# Battery.net
KiCad netlist of a schematic drawn in Altium Designer
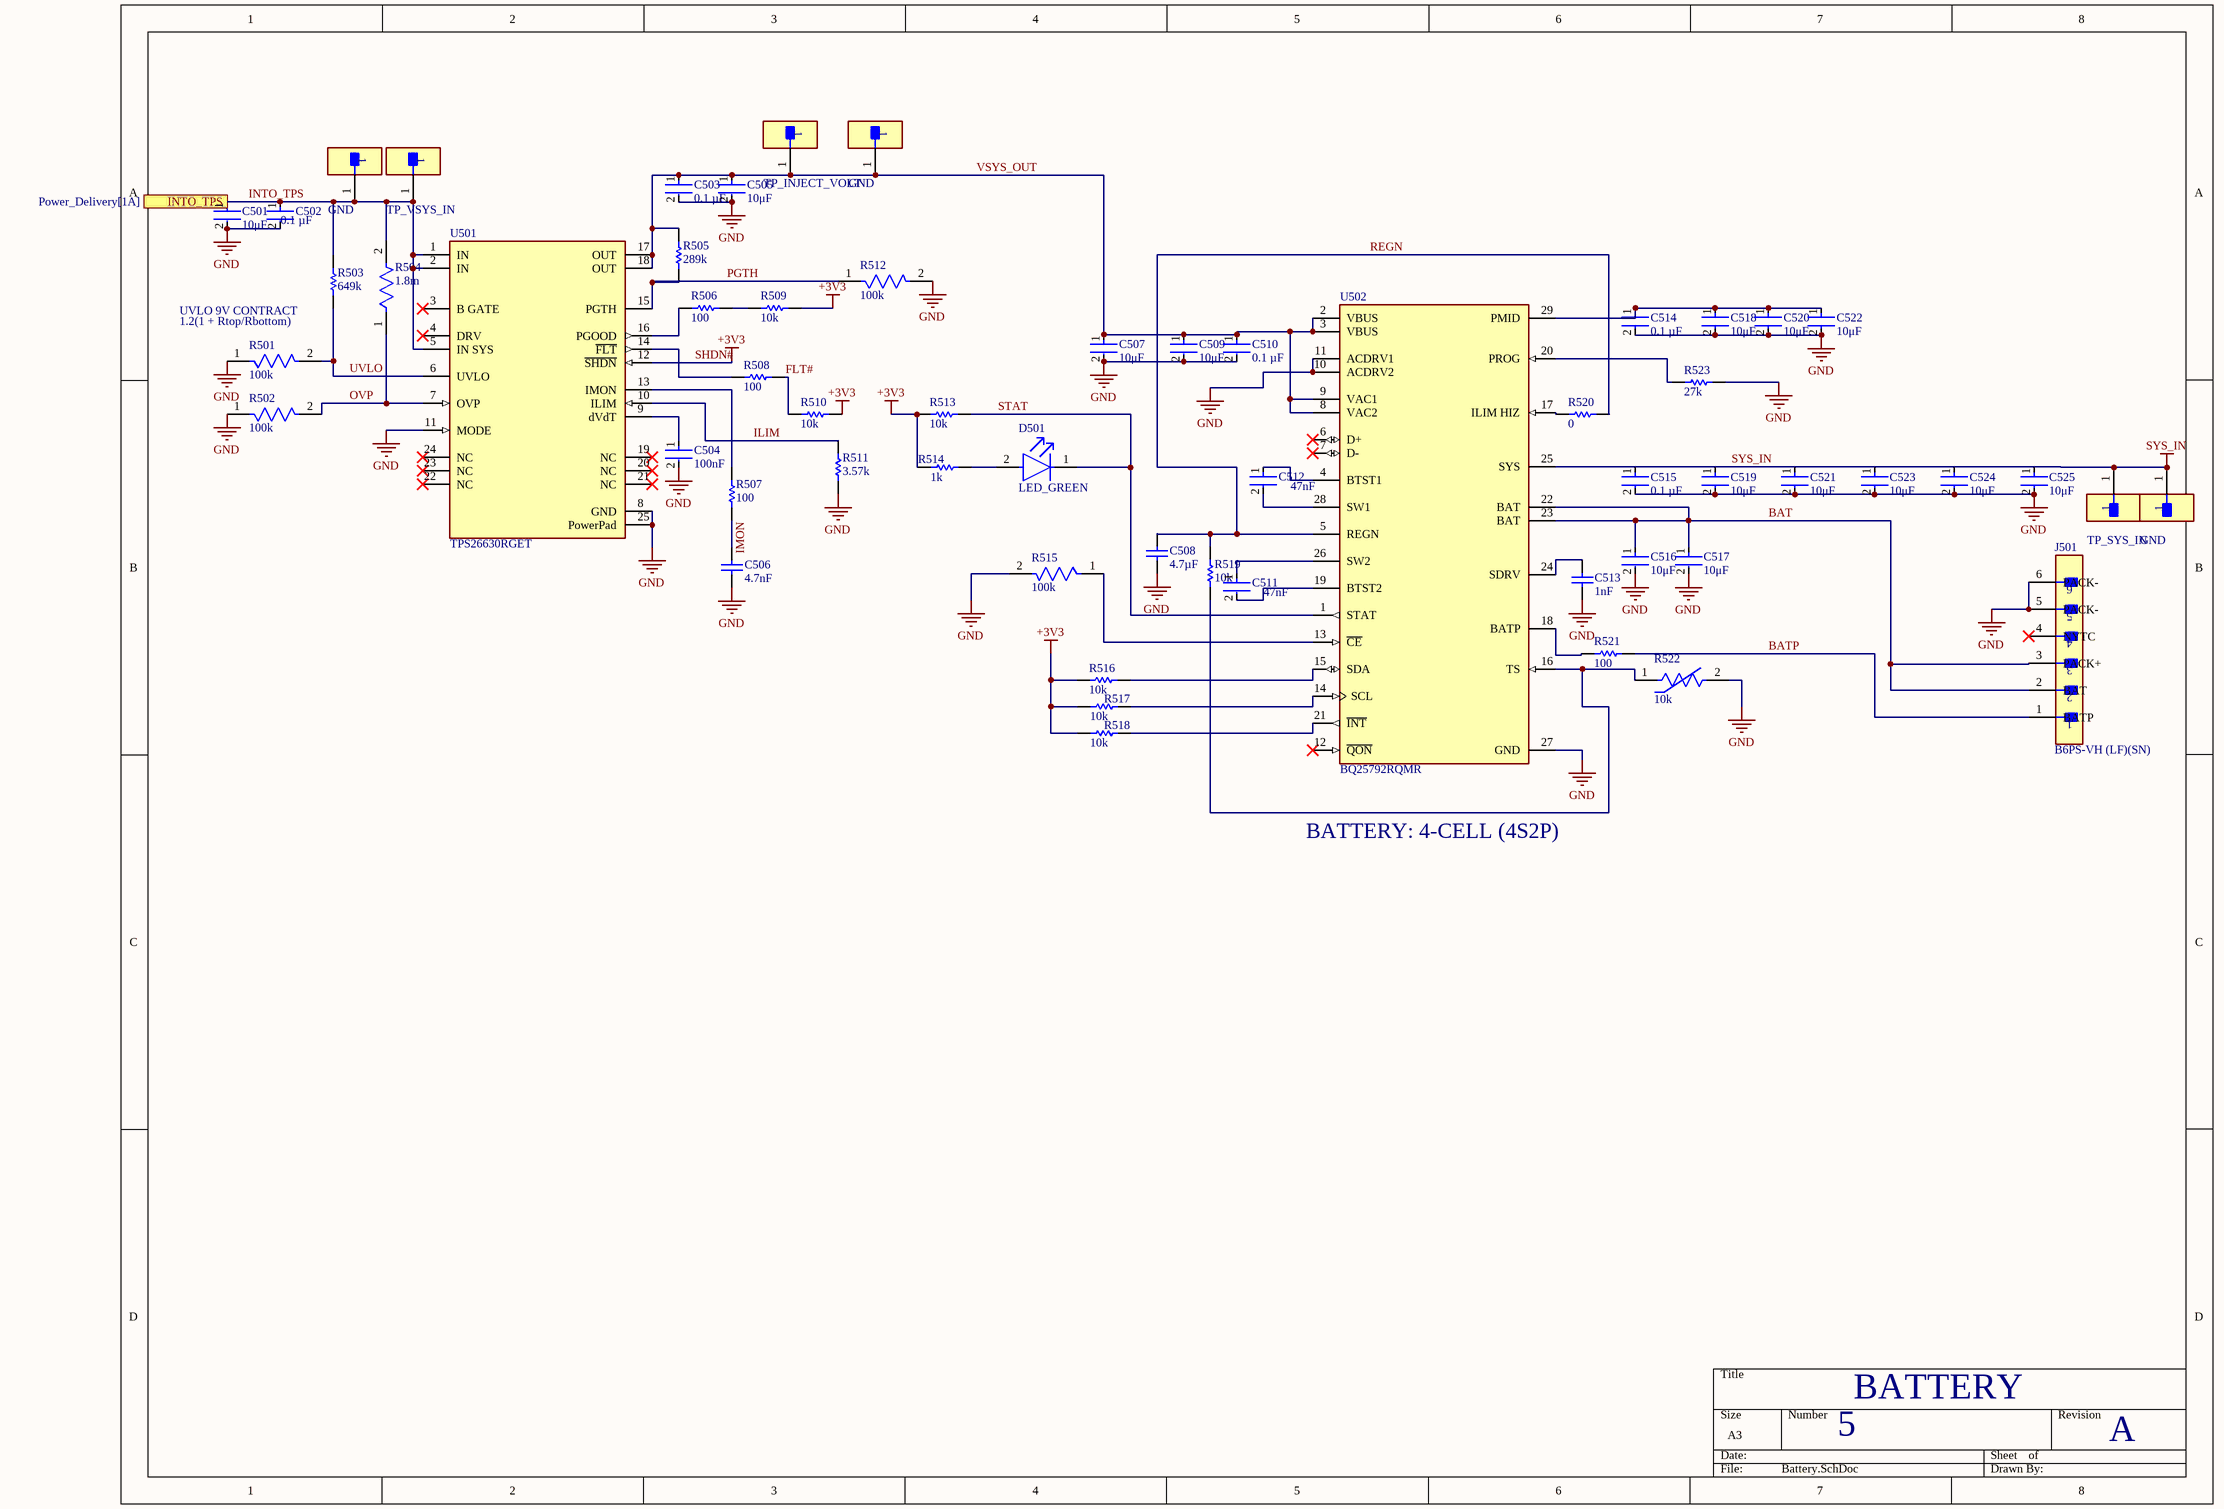
[diagram p0: Battery.SchDoc]

(export (version "E")
  (design (tool "Eeschema 10.0.6"))
  (components
    (comp (ref "C501")
      (value "10μF")
      (footprint "FP-GRM31C-0_2-e0_3_0_8-MFG")
      (description "Chip Multilayer Ceramic Capacitors for General Purpose, 1206, 10uF, X7R, 15%, 10%, 25V")
      (fields (field (name "TOLERANCE") "10%") (field (name "VOLTAGE") "25V"))
      (libsource (lib "Altium Content Vault") (part "02cd4be3c70576c341d710602a673aa"))
    )
    (comp (ref "C502")
      (value "0.1 µF")
      (footprint "FP-GRM155-0_05-IPC_B")
      (description "Chip Multilayer Ceramic Capacitors for General Purpose, 0402, 0.10uF, X7R, 15%, 10%, 50V")
      (fields (field (name "TOLERANCE") "10%"))
      (libsource (lib "Altium Content Vault") (part "02cd4be3c70576c341d710602a673aa"))
    )
    (comp (ref "C503")
      (value "0.1 µF")
      (footprint "FP-GRM155-0_05-IPC_B")
      (description "Chip Multilayer Ceramic Capacitors for General Purpose, 0402, 0.10uF, X7R, 15%, 10%, 50V")
      (fields (field (name "TOLERANCE") "10%"))
      (libsource (lib "Altium Content Vault") (part "02cd4be3c70576c341d710602a673aa"))
    )
    (comp (ref "C504")
      (value "100nF")
      (footprint "FP-GRM155-0_05-IPC_C")
      (description "Chip Multilayer Ceramic Capacitors for General Purpose, 0402, 0.10uF, X7R, 15%, 10%, 25V")
      (fields (field (name "TOLERANCE") "10%"))
      (libsource (lib "Altium Content Vault") (part "02cd4be3c70576c341d710602a673aa"))
    )
    (comp (ref "C505")
      (value "10μF")
      (footprint "FP-GRM31C-0_2-e0_3_0_8-MFG")
      (description "Chip Multilayer Ceramic Capacitors for General Purpose, 1206, 10uF, X7R, 15%, 10%, 25V")
      (fields (field (name "TOLERANCE") "10%") (field (name "VOLTAGE") "25V"))
      (libsource (lib "Altium Content Vault") (part "02cd4be3c70576c341d710602a673aa"))
    )
    (comp (ref "C506")
      (value "4.7nF")
      (footprint "CAPC1005X55X25LL05T10")
      (fields (field (name "MANUFACTURER") "Murata") (field (name "PART NUMBER") "GRM155R71C472KA01D"))
      (libsource (lib "Altium Content Vault") (part "CAP"))
    )
    (comp (ref "C507")
      (value "10μF")
      (footprint "FP-GRM31C-0_2-e0_3_0_8-MFG")
      (description "Chip Multilayer Ceramic Capacitors for General Purpose, 1206, 10uF, X7R, 15%, 10%, 25V")
      (fields (field (name "TOLERANCE") "10%") (field (name "VOLTAGE") "25V"))
      (libsource (lib "Altium Content Vault") (part "02cd4be3c70576c341d710602a673aa"))
    )
    (comp (ref "C508")
      (value "4.7µF")
      (footprint "CAPC1608X90X35NL10T15")
      (fields (field (name "MANUFACTURER") "Murata") (field (name "PART NUMBER") "GRM188R61A475KE15D"))
      (libsource (lib "Altium Content Vault") (part "CAP"))
    )
    (comp (ref "C509")
      (value "10μF")
      (footprint "FP-GRM31C-0_2-e0_3_0_8-MFG")
      (description "Chip Multilayer Ceramic Capacitors for General Purpose, 1206, 10uF, X7R, 15%, 10%, 25V")
      (fields (field (name "TOLERANCE") "10%") (field (name "VOLTAGE") "25V"))
      (libsource (lib "Altium Content Vault") (part "02cd4be3c70576c341d710602a673aa"))
    )
    (comp (ref "C510")
      (value "0.1 µF")
      (footprint "FP-GRM155-0_05-IPC_B")
      (description "Chip Multilayer Ceramic Capacitors for General Purpose, 0402, 0.10uF, X7R, 15%, 10%, 50V")
      (fields (field (name "TOLERANCE") "10%"))
      (libsource (lib "Altium Content Vault") (part "02cd4be3c70576c341d710602a673aa"))
    )
    (comp (ref "C511")
      (value "47nF")
      (footprint "FP-GRM155-0_05-MFG")
      (description "Chip Multilayer Ceramic Capacitors for General Purpose, 0402, 47000pF, X7R, 15%, 10%, 50V")
      (fields (field (name "TOLERANCE") "10%"))
      (libsource (lib "Altium Content Vault") (part "02cd4be3c70576c341d710602a673aa"))
    )
    (comp (ref "C512")
      (value "47nF")
      (footprint "FP-GRM155-0_05-MFG")
      (description "Chip Multilayer Ceramic Capacitors for General Purpose, 0402, 47000pF, X7R, 15%, 10%, 50V")
      (fields (field (name "TOLERANCE") "10%"))
      (libsource (lib "Altium Content Vault") (part "02cd4be3c70576c341d710602a673aa"))
    )
    (comp (ref "C513")
      (value "1nF")
      (footprint "CAPC1005X55X25ML5T10")
      (description "Chip Capacitor, 1 nF, +/- 10%, 50 V, -55 to 125 degC, 0402 (1005 Metric), RoHS, Tape and Reel")
      (fields (field (name "TOLERANCE") "10%"))
      (libsource (lib "Altium Content Vault") (part "CAP-NP-2"))
    )
    (comp (ref "C514")
      (value "0.1 µF")
      (footprint "FP-GRM155-0_05-IPC_B")
      (description "Chip Multilayer Ceramic Capacitors for General Purpose, 0402, 0.10uF, X7R, 15%, 10%, 50V")
      (fields (field (name "TOLERANCE") "10%"))
      (libsource (lib "Altium Content Vault") (part "02cd4be3c70576c341d710602a673aa"))
    )
    (comp (ref "C515")
      (value "0.1 µF")
      (footprint "FP-GRM155-0_05-IPC_B")
      (description "Chip Multilayer Ceramic Capacitors for General Purpose, 0402, 0.10uF, X7R, 15%, 10%, 50V")
      (fields (field (name "TOLERANCE") "10%"))
      (libsource (lib "Altium Content Vault") (part "02cd4be3c70576c341d710602a673aa"))
    )
    (comp (ref "C516")
      (value "10μF")
      (footprint "FP-GRM31C-0_2-e0_3_0_8-MFG")
      (description "Chip Multilayer Ceramic Capacitors for General Purpose, 1206, 10uF, X7R, 15%, 10%, 25V")
      (fields (field (name "TOLERANCE") "10%") (field (name "VOLTAGE") "25V"))
      (libsource (lib "Altium Content Vault") (part "02cd4be3c70576c341d710602a673aa"))
    )
    (comp (ref "C517")
      (value "10μF")
      (footprint "FP-GRM31C-0_2-e0_3_0_8-MFG")
      (description "Chip Multilayer Ceramic Capacitors for General Purpose, 1206, 10uF, X7R, 15%, 10%, 25V")
      (fields (field (name "TOLERANCE") "10%") (field (name "VOLTAGE") "25V"))
      (libsource (lib "Altium Content Vault") (part "02cd4be3c70576c341d710602a673aa"))
    )
    (comp (ref "C518")
      (value "10μF")
      (footprint "FP-GRM31C-0_2-e0_3_0_8-MFG")
      (description "Chip Multilayer Ceramic Capacitors for General Purpose, 1206, 10uF, X7R, 15%, 10%, 25V")
      (fields (field (name "TOLERANCE") "10%") (field (name "VOLTAGE") "25V"))
      (libsource (lib "Altium Content Vault") (part "02cd4be3c70576c341d710602a673aa"))
    )
    (comp (ref "C519")
      (value "10μF")
      (footprint "FP-GRM31C-0_2-e0_3_0_8-MFG")
      (description "Chip Multilayer Ceramic Capacitors for General Purpose, 1206, 10uF, X7R, 15%, 10%, 25V")
      (fields (field (name "TOLERANCE") "10%") (field (name "VOLTAGE") "25V"))
      (libsource (lib "Altium Content Vault") (part "02cd4be3c70576c341d710602a673aa"))
    )
    (comp (ref "C520")
      (value "10μF")
      (footprint "FP-GRM31C-0_2-e0_3_0_8-MFG")
      (description "Chip Multilayer Ceramic Capacitors for General Purpose, 1206, 10uF, X7R, 15%, 10%, 25V")
      (fields (field (name "TOLERANCE") "10%") (field (name "VOLTAGE") "25V"))
      (libsource (lib "Altium Content Vault") (part "02cd4be3c70576c341d710602a673aa"))
    )
    (comp (ref "C521")
      (value "10μF")
      (footprint "FP-GRM31C-0_2-e0_3_0_8-MFG")
      (description "Chip Multilayer Ceramic Capacitors for General Purpose, 1206, 10uF, X7R, 15%, 10%, 25V")
      (fields (field (name "TOLERANCE") "10%") (field (name "VOLTAGE") "25V"))
      (libsource (lib "Altium Content Vault") (part "02cd4be3c70576c341d710602a673aa"))
    )
    (comp (ref "C522")
      (value "10μF")
      (footprint "FP-GRM31C-0_2-e0_3_0_8-MFG")
      (description "Chip Multilayer Ceramic Capacitors for General Purpose, 1206, 10uF, X7R, 15%, 10%, 25V")
      (fields (field (name "TOLERANCE") "10%") (field (name "VOLTAGE") "25V"))
      (libsource (lib "Altium Content Vault") (part "02cd4be3c70576c341d710602a673aa"))
    )
    (comp (ref "C523")
      (value "10μF")
      (footprint "FP-GRM31C-0_2-e0_3_0_8-MFG")
      (description "Chip Multilayer Ceramic Capacitors for General Purpose, 1206, 10uF, X7R, 15%, 10%, 25V")
      (fields (field (name "TOLERANCE") "10%") (field (name "VOLTAGE") "25V"))
      (libsource (lib "Altium Content Vault") (part "02cd4be3c70576c341d710602a673aa"))
    )
    (comp (ref "C524")
      (value "10μF")
      (footprint "FP-GRM31C-0_2-e0_3_0_8-MFG")
      (description "Chip Multilayer Ceramic Capacitors for General Purpose, 1206, 10uF, X7R, 15%, 10%, 25V")
      (fields (field (name "TOLERANCE") "10%") (field (name "VOLTAGE") "25V"))
      (libsource (lib "Altium Content Vault") (part "02cd4be3c70576c341d710602a673aa"))
    )
    (comp (ref "C525")
      (value "10μF")
      (footprint "FP-GRM31C-0_2-e0_3_0_8-MFG")
      (description "Chip Multilayer Ceramic Capacitors for General Purpose, 1206, 10uF, X7R, 15%, 10%, 25V")
      (fields (field (name "TOLERANCE") "10%") (field (name "VOLTAGE") "25V"))
      (libsource (lib "Altium Content Vault") (part "02cd4be3c70576c341d710602a673aa"))
    )
    (comp (ref "D501")
      (value "LED_GREEN")
      (footprint "FP-SML-D12-MFG")
      (description "LED YLW/GREEN DIFFUSED 1608 SMD")
      (fields (field (name "MANUFACTURER PART NUMBER") "SML-D12M1WT86") (field (name "MANUFACTURER") "Rohm"))
      (libsource (lib "Altium Content Vault") (part "8706943c75ba83719d021d2fdc84c58"))
    )
    (comp (ref "J501")
      (value "B6PS-VH (LF)(SN)")
      (footprint "FP-B6PS-VH_LF_SN-MFG")
      (description "CONN HEADER R/A 6POS 3.96MM")
      (libsource (lib "Altium Content Vault") (part "f2cb566baf1c37ab5a3b8e90bbeafd6"))
    )
    (comp (ref "R501")
      (value "100k")
      (footprint "FP-RC0402-0_4-IPC_A")
      (description "RES 100K OHM 5% 1/16W 0402")
      (fields (field (name "TOLERANCE") "5%"))
      (libsource (lib "Altium Content Vault") (part "1029c3af85768c4190bb7ad29bc67b5"))
    )
    (comp (ref "R502")
      (value "100k")
      (footprint "FP-RC0402-0_4-IPC_A")
      (description "RES 100K OHM 5% 1/16W 0402")
      (fields (field (name "TOLERANCE") "5%"))
      (libsource (lib "Altium Content Vault") (part "1029c3af85768c4190bb7ad29bc67b5"))
    )
    (comp (ref "R503")
      (value "649k")
      (footprint "RESC1005X40X25ML05T10")
      (fields (field (name "PART NUMBER") "RC0402FR-07649KL") (field (name "MANUFACTURER") "Yageo / Phycomp"))
      (libsource (lib "Altium Content Vault") (part "RES"))
    )
    (comp (ref "R504")
      (value "1.8m")
      (footprint "FP-CRCW0402-e3-MFG")
      (description "RES Thick Film, 1.78MΩ, 1%, 0.063W, 100ppm/°C, 0402")
      (fields (field (name "TOLERANCE") "1%"))
      (libsource (lib "Altium Content Vault") (part "1029c3af85768c4190bb7ad29bc67b5"))
    )
    (comp (ref "R505")
      (value "289k")
      (footprint "RESC1005X40X25LL05T10")
      (fields (field (name "PART NUMBER") "RC0402FR-07287KL") (field (name "MANUFACTURER") "Yageo"))
      (libsource (lib "Altium Content Vault") (part "RES"))
    )
    (comp (ref "R506")
      (value "100")
      (footprint "RESC1005X40X25ML05T10")
      (fields (field (name "PART NUMBER") "RC0402FR-07100RL") (field (name "MANUFACTURER") "Yageo / Phycomp"))
      (libsource (lib "Altium Content Vault") (part "RES"))
    )
    (comp (ref "R507")
      (value "100")
      (footprint "RESC1005X40X25ML05T10")
      (fields (field (name "PART NUMBER") "RC0402FR-07100RL") (field (name "MANUFACTURER") "Yageo / Phycomp"))
      (libsource (lib "Altium Content Vault") (part "RES"))
    )
    (comp (ref "R508")
      (value "100")
      (footprint "RESC1005X40X25ML05T10")
      (fields (field (name "PART NUMBER") "RC0402FR-07100RL") (field (name "MANUFACTURER") "Yageo / Phycomp"))
      (libsource (lib "Altium Content Vault") (part "RES"))
    )
    (comp (ref "R509")
      (value "10k")
      (footprint "RESC1005X40X25LL05T10")
      (fields (field (name "PART NUMBER") "RC0402FR-0710KL") (field (name "MANUFACTURER") "Yageo / Phycomp"))
      (libsource (lib "Altium Content Vault") (part "RES"))
    )
    (comp (ref "R510")
      (value "10k")
      (footprint "RESC1005X40X25LL05T10")
      (fields (field (name "PART NUMBER") "RC0402FR-0710KL") (field (name "MANUFACTURER") "Yageo / Phycomp"))
      (libsource (lib "Altium Content Vault") (part "RES"))
    )
    (comp (ref "R511")
      (value "3.57k")
      (footprint "RESC1005X40X25ML05T10")
      (fields (field (name "PART NUMBER") "RC0402FR-073K57L") (field (name "MANUFACTURER") "Yageo"))
      (libsource (lib "Altium Content Vault") (part "RES"))
    )
    (comp (ref "R512")
      (value "100k")
      (footprint "FP-RC0402-0_4-IPC_A")
      (description "RES 100K OHM 5% 1/16W 0402")
      (fields (field (name "TOLERANCE") "5%"))
      (libsource (lib "Altium Content Vault") (part "1029c3af85768c4190bb7ad29bc67b5"))
    )
    (comp (ref "R513")
      (value "10k")
      (footprint "RESC1005X40X25LL05T10")
      (fields (field (name "PART NUMBER") "RC0402FR-0710KL") (field (name "MANUFACTURER") "Yageo / Phycomp"))
      (libsource (lib "Altium Content Vault") (part "RES"))
    )
    (comp (ref "R514")
      (value "1k")
      (footprint "RESC3216X60X45ML15T20")
      (description "Chip Resistor, 1 KOhm, +/- 1%, 0.25 W, -55 to 155 degC, 1206 (3216 Metric), RoHS, Tape and Reel")
      (fields (field (name "MANUFACTURER") "Vishay Semiconductor") (field (name "TOLERANCE") "1%"))
      (libsource (lib "Altium Content Vault") (part "RES-2"))
    )
    (comp (ref "R515")
      (value "100k")
      (footprint "FP-RC0402-0_4-IPC_A")
      (description "RES 100K OHM 5% 1/16W 0402")
      (fields (field (name "TOLERANCE") "5%"))
      (libsource (lib "Altium Content Vault") (part "1029c3af85768c4190bb7ad29bc67b5"))
    )
    (comp (ref "R516")
      (value "10k")
      (footprint "RESC1005X40X25LL05T10")
      (fields (field (name "PART NUMBER") "RC0402FR-0710KL") (field (name "MANUFACTURER") "Yageo / Phycomp"))
      (libsource (lib "Altium Content Vault") (part "RES"))
    )
    (comp (ref "R517")
      (value "10k")
      (footprint "RESC1005X40X25LL05T10")
      (fields (field (name "PART NUMBER") "RC0402FR-0710KL") (field (name "MANUFACTURER") "Yageo / Phycomp"))
      (libsource (lib "Altium Content Vault") (part "RES"))
    )
    (comp (ref "R518")
      (value "10k")
      (footprint "RESC1005X40X25LL05T10")
      (fields (field (name "PART NUMBER") "RC0402FR-0710KL") (field (name "MANUFACTURER") "Yageo / Phycomp"))
      (libsource (lib "Altium Content Vault") (part "RES"))
    )
    (comp (ref "R519")
      (value "10k")
      (footprint "RESC1005X40X25LL05T10")
      (fields (field (name "PART NUMBER") "RC0402FR-0710KL") (field (name "MANUFACTURER") "Yageo / Phycomp"))
      (libsource (lib "Altium Content Vault") (part "RES"))
    )
    (comp (ref "R520")
      (value "0")
      (footprint "RESC1005X40X25NL05T10")
      (fields (field (name "MANUFACTURER") "Yageo / Phycomp") (field (name "PART NUMBER") "RC0402JR-070RL"))
      (libsource (lib "Altium Content Vault") (part "RES"))
    )
    (comp (ref "R521")
      (value "100")
      (footprint "RESC1005X40X25ML05T10")
      (fields (field (name "PART NUMBER") "RC0402FR-07100RL") (field (name "MANUFACTURER") "Yageo / Phycomp"))
      (libsource (lib "Altium Content Vault") (part "RES"))
    )
    (comp (ref "R522")
      (value "10k")
      (footprint "FP-NCP15-NCU15-0_05-IPC_C")
      (description "NTC Thermistor for Temperature Sensor, 0402, 10kΩ, 1%, 0.1mA, 5V")
      (fields (field (name "TOLERANCE") "1%"))
      (libsource (lib "Altium Content Vault") (part "3b148a6ebabc5fb4d708a66c052d352"))
    )
    (comp (ref "R523")
      (value "27k")
      (footprint "RESC1005X40X25LL05T10")
      (fields (field (name "MANUFACTURER") "Yageo / Phycomp") (field (name "PART NUMBER") "RC0402FR-0727KL"))
      (libsource (lib "Altium Content Vault") (part "RES"))
    )
    (comp (ref "TP500")
      (value "GND")
      (footprint "FP-S2751-46R-MFG")
      (description "PC TEST POINT NATURAL")
      (libsource (lib "Altium Content Vault") (part "dd45045ce8184df9e99e12baf3f412c"))
    )
    (comp (ref "TP501")
      (value "TP_VSYS_IN")
      (footprint "FP-S2751-46R-MFG")
      (description "PC TEST POINT NATURAL")
      (libsource (lib "Altium Content Vault") (part "dd45045ce8184df9e99e12baf3f412c"))
    )
    (comp (ref "TP502")
      (value "TP_INJECT_VOLT")
      (footprint "FP-S2751-46R-MFG")
      (description "PC TEST POINT NATURAL")
      (libsource (lib "Altium Content Vault") (part "dd45045ce8184df9e99e12baf3f412c"))
    )
    (comp (ref "TP503")
      (value "GND")
      (footprint "FP-S2751-46R-MFG")
      (description "PC TEST POINT NATURAL")
      (libsource (lib "Altium Content Vault") (part "dd45045ce8184df9e99e12baf3f412c"))
    )
    (comp (ref "TP504")
      (value "TP_SYS_IN")
      (footprint "FP-S2751-46R-MFG")
      (description "PC TEST POINT NATURAL")
      (libsource (lib "") (part "dd45045ce8184df9e99e12baf3f412c_1"))
    )
    (comp (ref "TP505")
      (value "GND")
      (footprint "FP-S2751-46R-MFG")
      (description "PC TEST POINT NATURAL")
      (libsource (lib "") (part "dd45045ce8184df9e99e12baf3f412c_1"))
    )
    (comp (ref "U501")
      (value "TPS26630RGET")
      (footprint "FP-RGE0024H-MFG")
      (description "POWER MANAGEMENT")
      (libsource (lib "Altium Content Vault") (part "92e6325a0b2cd7354d0d77963e83935"))
    )
    (comp (ref "U502")
      (value "BQ25792RQMR")
      (footprint "FP-RQM0029A-MFG")
      (description "I2C CONTROLLED, 5-A, 1-4 CELL BU")
      (libsource (lib "Altium Content Vault") (part "43137d39c585c4e49e3b8f41bbae565"))
    )
  )
  (nets
    (net (code "1") (name "+3V3") (class "Default")
      (node (ref "R509") (pin "2") (pinfunction "2_2") (pintype "passive"))
      (node (ref "R510") (pin "2") (pinfunction "2_2") (pintype "passive"))
      (node (ref "R513") (pin "1") (pinfunction "1_1") (pintype "passive"))
      (node (ref "R514") (pin "2") (pinfunction "2_2") (pintype "passive"))
      (node (ref "R516") (pin "1") (pinfunction "1_1") (pintype "passive"))
      (node (ref "R517") (pin "1") (pinfunction "1_1") (pintype "passive"))
      (node (ref "R518") (pin "1") (pinfunction "1_1") (pintype "passive"))
      (node (ref "U501") (pin "12") (pinfunction "~{SHDN}_12") (pintype "input"))
    )
    (net (code "2") (name "/BAT") (class "Default")
      (node (ref "C516") (pin "1") (pinfunction "1_1") (pintype "passive"))
      (node (ref "C517") (pin "1") (pinfunction "1_1") (pintype "passive"))
      (node (ref "J501") (pin "2") (pinfunction "BAT_2") (pintype "passive"))
      (node (ref "J501") (pin "3") (pinfunction "PACK+_3") (pintype "passive"))
      (node (ref "U502") (pin "22") (pinfunction "BAT_22") (pintype "power_in"))
      (node (ref "U502") (pin "23") (pinfunction "BAT_23") (pintype "power_in"))
    )
    (net (code "3") (name "/BATP") (class "Default")
      (node (ref "J501") (pin "1") (pinfunction "BATP_1") (pintype "passive"))
      (node (ref "R521") (pin "2") (pinfunction "2_2") (pintype "passive"))
    )
    (net (code "4") (name "/FLT#") (class "Default")
      (node (ref "R508") (pin "2") (pinfunction "2_2") (pintype "passive"))
      (node (ref "R510") (pin "1") (pinfunction "1_1") (pintype "passive"))
    )
    (net (code "5") (name "/ILIM") (class "Default")
      (node (ref "R511") (pin "2") (pinfunction "2_2") (pintype "passive"))
      (node (ref "U501") (pin "10") (pinfunction "ILIM_10") (pintype "input"))
    )
    (net (code "6") (name "/IMON") (class "Default")
      (node (ref "C506") (pin "2") (pinfunction "2_2") (pintype "passive"))
      (node (ref "R507") (pin "1") (pinfunction "1_1") (pintype "passive"))
    )
    (net (code "7") (name "/INTO_TPS") (class "Default")
      (node (ref "C501") (pin "1") (pinfunction "1_1") (pintype "passive"))
      (node (ref "C502") (pin "1") (pinfunction "1_1") (pintype "passive"))
      (node (ref "R503") (pin "2") (pinfunction "2_2") (pintype "passive"))
      (node (ref "R504") (pin "2") (pinfunction "2_2") (pintype "passive"))
      (node (ref "TP500") (pin "1") (pinfunction "1_1") (pintype "passive"))
      (node (ref "TP501") (pin "1") (pinfunction "1_1") (pintype "passive"))
      (node (ref "U501") (pin "1") (pinfunction "IN_1") (pintype "power_in"))
      (node (ref "U501") (pin "2") (pinfunction "IN_2") (pintype "power_in"))
      (node (ref "U501") (pin "5") (pinfunction "IN_SYS_5") (pintype "power_in"))
    )
    (net (code "8") (name "/OVP") (class "Default")
      (node (ref "R502") (pin "2") (pinfunction "2_2") (pintype "passive"))
      (node (ref "R504") (pin "1") (pinfunction "1_1") (pintype "passive"))
      (node (ref "U501") (pin "7") (pinfunction "OVP_7") (pintype "input"))
    )
    (net (code "9") (name "/PGTH") (class "Default")
      (node (ref "R505") (pin "1") (pinfunction "1_1") (pintype "passive"))
      (node (ref "R512") (pin "1") (pinfunction "1_1") (pintype "passive"))
      (node (ref "U501") (pin "15") (pinfunction "PGTH_15") (pintype "passive"))
    )
    (net (code "10") (name "/REGN") (class "Default")
      (node (ref "C508") (pin "2") (pinfunction "2_2") (pintype "passive"))
      (node (ref "R519") (pin "1") (pinfunction "1_1") (pintype "passive"))
      (node (ref "R520") (pin "2") (pinfunction "2_2") (pintype "passive"))
      (node (ref "U502") (pin "5") (pinfunction "REGN_5") (pintype "power_in"))
    )
    (net (code "11") (name "/STAT") (class "Default")
      (node (ref "D501") (pin "1") (pinfunction "C_1") (pintype "passive"))
      (node (ref "R513") (pin "2") (pinfunction "2_2") (pintype "passive"))
      (node (ref "U502") (pin "1") (pinfunction "STAT_1") (pintype "output"))
    )
    (net (code "12") (name "/UVLO") (class "Default")
      (node (ref "R501") (pin "2") (pinfunction "2_2") (pintype "passive"))
      (node (ref "R503") (pin "1") (pinfunction "1_1") (pintype "passive"))
      (node (ref "U501") (pin "6") (pinfunction "UVLO_6") (pintype "passive"))
    )
    (net (code "13") (name "/VSYS_OUT") (class "Default")
      (node (ref "C503") (pin "1") (pinfunction "1_1") (pintype "passive"))
      (node (ref "C505") (pin "1") (pinfunction "1_1") (pintype "passive"))
      (node (ref "C507") (pin "1") (pinfunction "1_1") (pintype "passive"))
      (node (ref "C509") (pin "1") (pinfunction "1_1") (pintype "passive"))
      (node (ref "C510") (pin "1") (pinfunction "1_1") (pintype "passive"))
      (node (ref "R505") (pin "2") (pinfunction "2_2") (pintype "passive"))
      (node (ref "TP502") (pin "1") (pinfunction "1_1") (pintype "passive"))
      (node (ref "TP503") (pin "1") (pinfunction "1_1") (pintype "passive"))
      (node (ref "U501") (pin "17") (pinfunction "OUT_17") (pintype "power_in"))
      (node (ref "U501") (pin "18") (pinfunction "OUT_18") (pintype "power_in"))
      (node (ref "U502") (pin "2") (pinfunction "VBUS_2") (pintype "power_in"))
      (node (ref "U502") (pin "3") (pinfunction "VBUS_3") (pintype "power_in"))
      (node (ref "U502") (pin "8") (pinfunction "VAC2_8") (pintype "power_in"))
      (node (ref "U502") (pin "9") (pinfunction "VAC1_9") (pintype "power_in"))
    )
    (net (code "14") (name "GND") (class "Default")
      (node (ref "C501") (pin "2") (pinfunction "2_2") (pintype "passive"))
      (node (ref "C502") (pin "2") (pinfunction "2_2") (pintype "passive"))
      (node (ref "C503") (pin "2") (pinfunction "2_2") (pintype "passive"))
      (node (ref "C504") (pin "2") (pinfunction "2_2") (pintype "passive"))
      (node (ref "C505") (pin "2") (pinfunction "2_2") (pintype "passive"))
      (node (ref "C506") (pin "1") (pinfunction "1_1") (pintype "passive"))
      (node (ref "C507") (pin "2") (pinfunction "2_2") (pintype "passive"))
      (node (ref "C508") (pin "1") (pinfunction "1_1") (pintype "passive"))
      (node (ref "C509") (pin "2") (pinfunction "2_2") (pintype "passive"))
      (node (ref "C510") (pin "2") (pinfunction "2_2") (pintype "passive"))
      (node (ref "C513") (pin "1") (pinfunction "1_1") (pintype "passive"))
      (node (ref "C514") (pin "2") (pinfunction "2_2") (pintype "passive"))
      (node (ref "C515") (pin "2") (pinfunction "2_2") (pintype "passive"))
      (node (ref "C516") (pin "2") (pinfunction "2_2") (pintype "passive"))
      (node (ref "C517") (pin "2") (pinfunction "2_2") (pintype "passive"))
      (node (ref "C518") (pin "2") (pinfunction "2_2") (pintype "passive"))
      (node (ref "C519") (pin "2") (pinfunction "2_2") (pintype "passive"))
      (node (ref "C520") (pin "2") (pinfunction "2_2") (pintype "passive"))
      (node (ref "C521") (pin "2") (pinfunction "2_2") (pintype "passive"))
      (node (ref "C522") (pin "2") (pinfunction "2_2") (pintype "passive"))
      (node (ref "C523") (pin "2") (pinfunction "2_2") (pintype "passive"))
      (node (ref "C524") (pin "2") (pinfunction "2_2") (pintype "passive"))
      (node (ref "C525") (pin "2") (pinfunction "2_2") (pintype "passive"))
      (node (ref "J501") (pin "5") (pinfunction "PACK-_5") (pintype "passive"))
      (node (ref "J501") (pin "6") (pinfunction "PACK-_6") (pintype "passive"))
      (node (ref "R501") (pin "1") (pinfunction "1_1") (pintype "passive"))
      (node (ref "R502") (pin "1") (pinfunction "1_1") (pintype "passive"))
      (node (ref "R511") (pin "1") (pinfunction "1_1") (pintype "passive"))
      (node (ref "R512") (pin "2") (pinfunction "2_2") (pintype "passive"))
      (node (ref "R515") (pin "2") (pinfunction "2_2") (pintype "passive"))
      (node (ref "R522") (pin "2") (pinfunction "2_2") (pintype "passive"))
      (node (ref "R523") (pin "2") (pinfunction "2_2") (pintype "passive"))
      (node (ref "U501") (pin "11") (pinfunction "MODE_11") (pintype "input"))
      (node (ref "U501") (pin "25") (pinfunction "PowerPad_25") (pintype "power_in"))
      (node (ref "U501") (pin "8") (pinfunction "GND_8") (pintype "power_in"))
      (node (ref "U502") (pin "10") (pinfunction "ACDRV2_10") (pintype "power_in"))
      (node (ref "U502") (pin "11") (pinfunction "ACDRV1_11") (pintype "power_in"))
      (node (ref "U502") (pin "27") (pinfunction "GND_27") (pintype "power_in"))
    )
    (net (code "15") (name "Net-(D501-A)") (class "Default")
      (node (ref "D501") (pin "2") (pinfunction "A_2") (pintype "passive"))
      (node (ref "R514") (pin "1") (pinfunction "1_1") (pintype "passive"))
    )
    (net (code "16") (name "Net-(R506-Pad2)") (class "Default")
      (node (ref "R506") (pin "2") (pinfunction "2_2") (pintype "passive"))
      (node (ref "R509") (pin "1") (pinfunction "1_1") (pintype "passive"))
    )
    (net (code "17") (name "Net-(U501-IMON)") (class "Default")
      (node (ref "R507") (pin "2") (pinfunction "2_2") (pintype "passive"))
      (node (ref "U501") (pin "13") (pinfunction "IMON_13") (pintype "passive"))
    )
    (net (code "18") (name "Net-(U501-PGOOD)") (class "Default")
      (node (ref "R506") (pin "1") (pinfunction "1_1") (pintype "passive"))
      (node (ref "U501") (pin "16") (pinfunction "PGOOD_16") (pintype "output"))
    )
    (net (code "19") (name "Net-(U501-dVdT)") (class "Default")
      (node (ref "C504") (pin "1") (pinfunction "1_1") (pintype "passive"))
      (node (ref "U501") (pin "9") (pinfunction "dVdT_9") (pintype "passive"))
    )
    (net (code "20") (name "Net-(U501-~{FLT})") (class "Default")
      (node (ref "R508") (pin "1") (pinfunction "1_1") (pintype "passive"))
      (node (ref "U501") (pin "14") (pinfunction "~{FLT}_14") (pintype "output"))
    )
    (net (code "21") (name "Net-(U502-BATP)") (class "Default")
      (node (ref "R521") (pin "1") (pinfunction "1_1") (pintype "passive"))
      (node (ref "U502") (pin "18") (pinfunction "BATP_18") (pintype "power_in"))
    )
    (net (code "22") (name "Net-(U502-BTST1)") (class "Default")
      (node (ref "C512") (pin "1") (pinfunction "1_1") (pintype "passive"))
      (node (ref "U502") (pin "4") (pinfunction "BTST1_4") (pintype "power_in"))
    )
    (net (code "23") (name "Net-(U502-BTST2)") (class "Default")
      (node (ref "C511") (pin "2") (pinfunction "2_2") (pintype "passive"))
      (node (ref "U502") (pin "19") (pinfunction "BTST2_19") (pintype "power_in"))
    )
    (net (code "24") (name "Net-(U502-ILIM_HIZ)") (class "Default")
      (node (ref "R520") (pin "1") (pinfunction "1_1") (pintype "passive"))
      (node (ref "U502") (pin "17") (pinfunction "ILIM_HIZ_17") (pintype "input"))
    )
    (net (code "25") (name "Net-(U502-PMID)") (class "Default")
      (node (ref "C514") (pin "1") (pinfunction "1_1") (pintype "passive"))
      (node (ref "C518") (pin "1") (pinfunction "1_1") (pintype "passive"))
      (node (ref "C520") (pin "1") (pinfunction "1_1") (pintype "passive"))
      (node (ref "C522") (pin "1") (pinfunction "1_1") (pintype "passive"))
      (node (ref "U502") (pin "29") (pinfunction "PMID_29") (pintype "power_in"))
    )
    (net (code "26") (name "Net-(U502-PROG)") (class "Default")
      (node (ref "R523") (pin "1") (pinfunction "1_1") (pintype "passive"))
      (node (ref "U502") (pin "20") (pinfunction "PROG_20") (pintype "input"))
    )
    (net (code "27") (name "Net-(U502-SCL)") (class "Default")
      (node (ref "R517") (pin "2") (pinfunction "2_2") (pintype "passive"))
      (node (ref "U502") (pin "14") (pinfunction "SCL_14") (pintype "input"))
    )
    (net (code "28") (name "Net-(U502-SDA)") (class "Default")
      (node (ref "R516") (pin "2") (pinfunction "2_2") (pintype "passive"))
      (node (ref "U502") (pin "15") (pinfunction "SDA_15") (pintype "bidirectional"))
    )
    (net (code "29") (name "Net-(U502-SDRV)") (class "Default")
      (node (ref "C513") (pin "2") (pinfunction "2_2") (pintype "passive"))
      (node (ref "U502") (pin "24") (pinfunction "SDRV_24") (pintype "power_in"))
    )
    (net (code "30") (name "Net-(U502-SW1)") (class "Default")
      (node (ref "C512") (pin "2") (pinfunction "2_2") (pintype "passive"))
      (node (ref "U502") (pin "28") (pinfunction "SW1_28") (pintype "power_in"))
    )
    (net (code "31") (name "Net-(U502-SW2)") (class "Default")
      (node (ref "C511") (pin "1") (pinfunction "1_1") (pintype "passive"))
      (node (ref "U502") (pin "26") (pinfunction "SW2_26") (pintype "power_in"))
    )
    (net (code "32") (name "Net-(U502-TS)") (class "Default")
      (node (ref "R519") (pin "2") (pinfunction "2_2") (pintype "passive"))
      (node (ref "R522") (pin "1") (pinfunction "1_1") (pintype "passive"))
      (node (ref "U502") (pin "16") (pinfunction "TS_16") (pintype "input"))
    )
    (net (code "33") (name "Net-(U502-~{CE})") (class "Default")
      (node (ref "R515") (pin "1") (pinfunction "1_1") (pintype "passive"))
      (node (ref "U502") (pin "13") (pinfunction "~{CE}_13") (pintype "input"))
    )
    (net (code "34") (name "Net-(U502-~{INT})") (class "Default")
      (node (ref "R518") (pin "2") (pinfunction "2_2") (pintype "passive"))
      (node (ref "U502") (pin "21") (pinfunction "~{INT}_21") (pintype "output"))
    )
    (net (code "35") (name "SYS_IN") (class "Default")
      (node (ref "TP504") (pin "1") (pinfunction "1_1") (pintype "passive"))
      (node (ref "TP505") (pin "1") (pinfunction "1_1") (pintype "passive"))
      (node (ref "U502") (pin "25") (pinfunction "SYS_25") (pintype "power_in"))
    )
    (net (code "36") (name "unconnected-(C515-Pad1)") (class "Default")
      (node (ref "C515") (pin "1") (pinfunction "1_1") (pintype "passive"))
    )
    (net (code "37") (name "unconnected-(C519-Pad1)") (class "Default")
      (node (ref "C519") (pin "1") (pinfunction "1_1") (pintype "passive"))
    )
    (net (code "38") (name "unconnected-(C521-Pad1)") (class "Default")
      (node (ref "C521") (pin "1") (pinfunction "1_1") (pintype "passive"))
    )
    (net (code "39") (name "unconnected-(C523-Pad1)") (class "Default")
      (node (ref "C523") (pin "1") (pinfunction "1_1") (pintype "passive"))
    )
    (net (code "40") (name "unconnected-(C524-Pad1)") (class "Default")
      (node (ref "C524") (pin "1") (pinfunction "1_1") (pintype "passive"))
    )
    (net (code "41") (name "unconnected-(C525-Pad1)") (class "Default")
      (node (ref "C525") (pin "1") (pinfunction "1_1") (pintype "passive"))
    )
    (net (code "42") (name "unconnected-(J501-NYTC-Pad4)") (class "Default")
      (node (ref "J501") (pin "4") (pinfunction "NYTC_4") (pintype "passive+no_connect"))
    )
    (net (code "43") (name "unconnected-(U501-B_GATE-Pad3)") (class "Default")
      (node (ref "U501") (pin "3") (pinfunction "B_GATE_3") (pintype "passive+no_connect"))
    )
    (net (code "44") (name "unconnected-(U501-DRV-Pad4)") (class "Default")
      (node (ref "U501") (pin "4") (pinfunction "DRV_4") (pintype "passive+no_connect"))
    )
    (net (code "45") (name "unconnected-(U501-NC-Pad19)") (class "Default")
      (node (ref "U501") (pin "19") (pinfunction "NC_19") (pintype "passive+no_connect"))
    )
    (net (code "46") (name "unconnected-(U501-NC-Pad20)") (class "Default")
      (node (ref "U501") (pin "20") (pinfunction "NC_20") (pintype "passive+no_connect"))
    )
    (net (code "47") (name "unconnected-(U501-NC-Pad21)") (class "Default")
      (node (ref "U501") (pin "21") (pinfunction "NC_21") (pintype "passive+no_connect"))
    )
    (net (code "48") (name "unconnected-(U501-NC-Pad22)") (class "Default")
      (node (ref "U501") (pin "22") (pinfunction "NC_22") (pintype "passive+no_connect"))
    )
    (net (code "49") (name "unconnected-(U501-NC-Pad23)") (class "Default")
      (node (ref "U501") (pin "23") (pinfunction "NC_23") (pintype "passive+no_connect"))
    )
    (net (code "50") (name "unconnected-(U501-NC-Pad24)") (class "Default")
      (node (ref "U501") (pin "24") (pinfunction "NC_24") (pintype "passive+no_connect"))
    )
    (net (code "51") (name "unconnected-(U502-D+-Pad6)") (class "Default")
      (node (ref "U502") (pin "6") (pinfunction "D+_6") (pintype "bidirectional+no_connect"))
    )
    (net (code "52") (name "unconnected-(U502-D--Pad7)") (class "Default")
      (node (ref "U502") (pin "7") (pinfunction "D-_7") (pintype "bidirectional+no_connect"))
    )
    (net (code "53") (name "unconnected-(U502-~{QON}-Pad12)") (class "Default")
      (node (ref "U502") (pin "12") (pinfunction "~{QON}_12") (pintype "input+no_connect"))
    )
  )
)
